# Display.net
KiCad netlist of a schematic drawn in Altium Designer
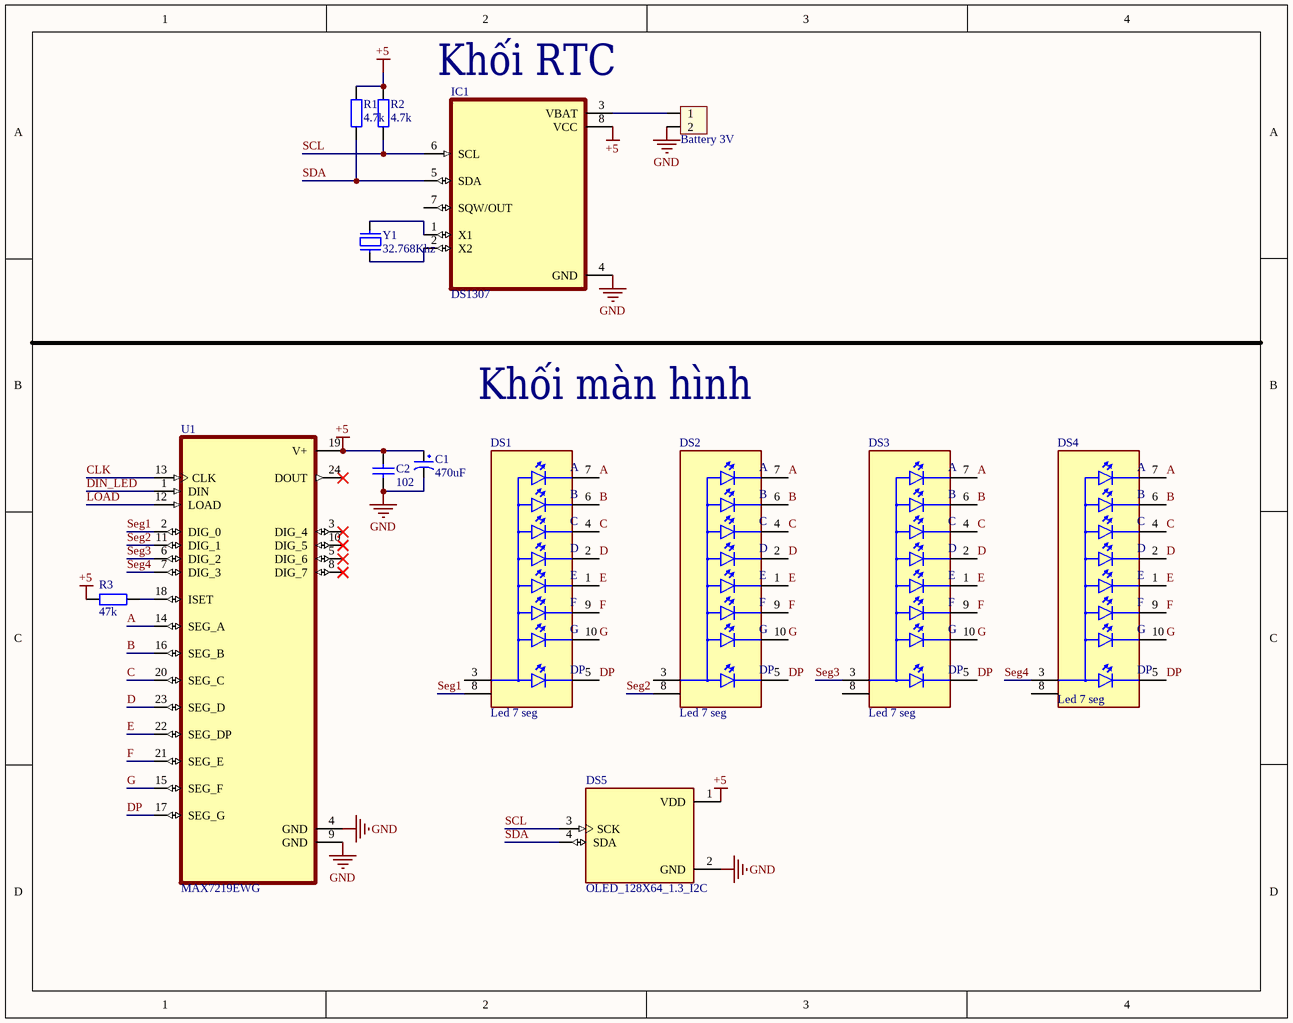
[diagram p0: Display.SchDoc]

(export (version "E")
  (design (tool "Eeschema 10.0.6"))
  (components
    (comp (ref "C1")
      (value "470uF")
      (footprint "TU HOA 8mm")
      (description "Cắm")
      (libsource (lib "Capacitor") (part "Tu Hoa 470uF 50V 10x17"))
    )
    (comp (ref "C2")
      (value "102")
      (footprint "tu 1206")
      (description "Dán")
      (libsource (lib "Capacitor") (part "Tu 1206 102 50V 10%"))
    )
    (comp (ref "DS1")
      (value "Led 7 seg")
      (footprint "LED_7Seg_1Inch:2.3_7-SEG_DIS")
      (fields (field (name "MF") "Broadcom Limited") (field (name "MP") "HDSP-511Y"))
      (libsource (lib "HDSP-511Y") (part "HDSP-511Y"))
    )
    (comp (ref "DS2")
      (value "Led 7 seg")
      (footprint "LED_7Seg_1Inch:2.3_7-SEG_DIS")
      (fields (field (name "MF") "Broadcom Limited") (field (name "MP") "HDSP-511Y"))
      (libsource (lib "HDSP-511Y") (part "HDSP-511Y"))
    )
    (comp (ref "DS3")
      (value "Led 7 seg")
      (footprint "LED_7Seg_1Inch:2.3_7-SEG_DIS")
      (fields (field (name "MF") "Broadcom Limited") (field (name "MP") "HDSP-511Y"))
      (libsource (lib "HDSP-511Y") (part "HDSP-511Y"))
    )
    (comp (ref "DS4")
      (value "Led 7 seg")
      (footprint "LED_7Seg_1Inch:2.3_7-SEG_DIS")
      (fields (field (name "MF") "Broadcom Limited") (field (name "MP") "HDSP-511Y"))
      (libsource (lib "HDSP-511Y") (part "HDSP-511Y"))
    )
    (comp (ref "DS5")
      (value "OLED_128X64_1.3_I2C")
      (footprint "LCD_OLED_128X64_1.3_I2C")
      (fields
        (field (name "MF") "UNIVERSAL-SOLDER Electronics Ltd")
        (field (name "MP") "OLED 128x64 1.3&quot; I2C")
      )
      (libsource (lib "OLED_128X64_1.3_I2C") (part "OLED_128X64_1.3_I2C"))
    )
    (comp (ref "H1")
      (value "Battery 3V")
      (footprint "Header 2P DC 2.54")
      (description "Cắm")
      (libsource (lib "Header") (part "Header 2P 2.54 Duc Cong"))
    )
    (comp (ref "IC1")
      (value "DS1307")
      (footprint "DIP794W47P254L991H457Q8")
      (description "Real Time Clock (RTC) IC Clock/Calendar 56B IÂ²C, 2-Wire Serial 8-SOIC (0.154, 3.90mm Width)")
      (fields (field (name "MF") "Maxim Integrated"))
      (libsource (lib "DS1307") (part "DS1307"))
    )
    (comp (ref "R1")
      (value "4.7k")
      (footprint "tro smd 1206")
      (description "Dán")
      (libsource (lib "Resistor") (part "Tro 1206 5% 1k"))
    )
    (comp (ref "R2")
      (value "4.7k")
      (footprint "tro smd 1206")
      (description "Dán")
      (libsource (lib "Resistor") (part "Tro 1206 5% 1k"))
    )
    (comp (ref "R3")
      (value "47k")
      (footprint "tro smd 1206")
      (description "Dán")
      (libsource (lib "Resistor") (part "Tro 1206 5% 1k"))
    )
    (comp (ref "U1")
      (value "MAX7219EWG")
      (footprint "DIP794W47P254L3054H457Q24")
      (description "LED Driver 64 Segment 330000uA Supply Current 24-Pin SOIC W Tube")
      (fields (field (name "MF") "Analog Devices") (field (name "MP") "MAX7219EWG+"))
      (libsource (lib "MAX7219EWG") (part "MAX7219EWG"))
    )
    (comp (ref "Y1")
      (value "32.768Khz")
      (footprint "Thach Anh 2 Chan 32,768 KHz")
      (description "Crystal For all Crystal 2pin.")
      (libsource (lib "Component") (part "Thach Anh 2 chan Cam"))
    )
  )
  (nets
    (net (code "1") (name "+5") (class "Default")
      (node (ref "C1") (pin "1") (pinfunction "1_1") (pintype "passive"))
      (node (ref "C2") (pin "1") (pinfunction "1_1") (pintype "passive"))
      (node (ref "DS5") (pin "1") (pinfunction "VDD_1") (pintype "power_in"))
      (node (ref "IC1") (pin "8") (pinfunction "VCC_8") (pintype "power_in"))
      (node (ref "R1") (pin "2") (pinfunction "2_2") (pintype "passive"))
      (node (ref "R2") (pin "2") (pinfunction "2_2") (pintype "passive"))
      (node (ref "R3") (pin "2") (pinfunction "2_2") (pintype "passive"))
      (node (ref "U1") (pin "19") (pinfunction "V+_19") (pintype "power_in"))
    )
    (net (code "2") (name "/A") (class "Default")
      (node (ref "DS1") (pin "7") (pinfunction "A_7") (pintype "passive"))
      (node (ref "DS2") (pin "7") (pinfunction "A_7") (pintype "passive"))
      (node (ref "DS3") (pin "7") (pinfunction "A_7") (pintype "passive"))
      (node (ref "DS4") (pin "7") (pinfunction "A_7") (pintype "passive"))
      (node (ref "U1") (pin "14") (pinfunction "SEG_A_14") (pintype "bidirectional"))
    )
    (net (code "3") (name "/B") (class "Default")
      (node (ref "DS1") (pin "6") (pinfunction "B_6") (pintype "passive"))
      (node (ref "DS2") (pin "6") (pinfunction "B_6") (pintype "passive"))
      (node (ref "DS3") (pin "6") (pinfunction "B_6") (pintype "passive"))
      (node (ref "DS4") (pin "6") (pinfunction "B_6") (pintype "passive"))
      (node (ref "U1") (pin "16") (pinfunction "SEG_B_16") (pintype "bidirectional"))
    )
    (net (code "4") (name "/C") (class "Default")
      (node (ref "DS1") (pin "4") (pinfunction "C_4") (pintype "passive"))
      (node (ref "DS2") (pin "4") (pinfunction "C_4") (pintype "passive"))
      (node (ref "DS3") (pin "4") (pinfunction "C_4") (pintype "passive"))
      (node (ref "DS4") (pin "4") (pinfunction "C_4") (pintype "passive"))
      (node (ref "U1") (pin "20") (pinfunction "SEG_C_20") (pintype "bidirectional"))
    )
    (net (code "5") (name "/CLK") (class "Default")
      (node (ref "U1") (pin "13") (pinfunction "CLK_13") (pintype "input"))
    )
    (net (code "6") (name "/D") (class "Default")
      (node (ref "DS1") (pin "2") (pinfunction "D_2") (pintype "passive"))
      (node (ref "DS2") (pin "2") (pinfunction "D_2") (pintype "passive"))
      (node (ref "DS3") (pin "2") (pinfunction "D_2") (pintype "passive"))
      (node (ref "DS4") (pin "2") (pinfunction "D_2") (pintype "passive"))
      (node (ref "U1") (pin "23") (pinfunction "SEG_D_23") (pintype "bidirectional"))
    )
    (net (code "7") (name "/DIN_LED") (class "Default")
      (node (ref "U1") (pin "1") (pinfunction "DIN_1") (pintype "input"))
    )
    (net (code "8") (name "/DP") (class "Default")
      (node (ref "DS1") (pin "5") (pinfunction "DP_5") (pintype "passive"))
      (node (ref "DS2") (pin "5") (pinfunction "DP_5") (pintype "passive"))
      (node (ref "DS3") (pin "5") (pinfunction "DP_5") (pintype "passive"))
      (node (ref "DS4") (pin "5") (pinfunction "DP_5") (pintype "passive"))
      (node (ref "U1") (pin "17") (pinfunction "SEG_G_17") (pintype "bidirectional"))
    )
    (net (code "9") (name "/E") (class "Default")
      (node (ref "DS1") (pin "1") (pinfunction "E_1") (pintype "passive"))
      (node (ref "DS2") (pin "1") (pinfunction "E_1") (pintype "passive"))
      (node (ref "DS3") (pin "1") (pinfunction "E_1") (pintype "passive"))
      (node (ref "DS4") (pin "1") (pinfunction "E_1") (pintype "passive"))
      (node (ref "U1") (pin "22") (pinfunction "SEG_DP_22") (pintype "bidirectional"))
    )
    (net (code "10") (name "/F") (class "Default")
      (node (ref "DS1") (pin "9") (pinfunction "F_9") (pintype "passive"))
      (node (ref "DS2") (pin "9") (pinfunction "F_9") (pintype "passive"))
      (node (ref "DS3") (pin "9") (pinfunction "F_9") (pintype "passive"))
      (node (ref "DS4") (pin "9") (pinfunction "F_9") (pintype "passive"))
      (node (ref "U1") (pin "21") (pinfunction "SEG_E_21") (pintype "bidirectional"))
    )
    (net (code "11") (name "/G") (class "Default")
      (node (ref "DS1") (pin "10") (pinfunction "G_10") (pintype "passive"))
      (node (ref "DS2") (pin "10") (pinfunction "G_10") (pintype "passive"))
      (node (ref "DS3") (pin "10") (pinfunction "G_10") (pintype "passive"))
      (node (ref "DS4") (pin "10") (pinfunction "G_10") (pintype "passive"))
      (node (ref "U1") (pin "15") (pinfunction "SEG_F_15") (pintype "bidirectional"))
    )
    (net (code "12") (name "/LOAD") (class "Default")
      (node (ref "U1") (pin "12") (pinfunction "LOAD_12") (pintype "input"))
    )
    (net (code "13") (name "/SCL") (class "Default")
      (node (ref "DS5") (pin "3") (pinfunction "SCK_3") (pintype "input"))
      (node (ref "IC1") (pin "6") (pinfunction "SCL_6") (pintype "input"))
      (node (ref "R2") (pin "1") (pinfunction "1_1") (pintype "passive"))
    )
    (net (code "14") (name "/SDA") (class "Default")
      (node (ref "DS5") (pin "4") (pinfunction "SDA_4") (pintype "bidirectional"))
      (node (ref "IC1") (pin "5") (pinfunction "SDA_5") (pintype "bidirectional"))
      (node (ref "R1") (pin "1") (pinfunction "1_1") (pintype "passive"))
    )
    (net (code "15") (name "/Seg1") (class "Default")
      (node (ref "DS1") (pin "8") (pinfunction "COM_8") (pintype "passive"))
      (node (ref "U1") (pin "2") (pinfunction "DIG_0_2") (pintype "bidirectional"))
    )
    (net (code "16") (name "/Seg2") (class "Default")
      (node (ref "DS2") (pin "8") (pinfunction "COM_8") (pintype "passive"))
      (node (ref "U1") (pin "11") (pinfunction "DIG_1_11") (pintype "bidirectional"))
    )
    (net (code "17") (name "/Seg3") (class "Default")
      (node (ref "DS3") (pin "3") (pinfunction "COM_3") (pintype "passive"))
      (node (ref "U1") (pin "6") (pinfunction "DIG_2_6") (pintype "bidirectional"))
    )
    (net (code "18") (name "/Seg4") (class "Default")
      (node (ref "DS4") (pin "3") (pinfunction "COM_3") (pintype "passive"))
      (node (ref "U1") (pin "7") (pinfunction "DIG_3_7") (pintype "bidirectional"))
    )
    (net (code "19") (name "GND") (class "Default")
      (node (ref "C1") (pin "2") (pinfunction "2_2") (pintype "passive"))
      (node (ref "C2") (pin "2") (pinfunction "2_2") (pintype "passive"))
      (node (ref "DS5") (pin "2") (pinfunction "GND_2") (pintype "power_in"))
      (node (ref "H1") (pin "2") (pinfunction "2_2") (pintype "passive"))
      (node (ref "IC1") (pin "4") (pinfunction "GND_4") (pintype "power_in"))
      (node (ref "U1") (pin "4") (pinfunction "GND_4") (pintype "power_in"))
      (node (ref "U1") (pin "9") (pinfunction "GND_9") (pintype "power_in"))
    )
    (net (code "20") (name "Net-(IC1-VBAT)") (class "Default")
      (node (ref "H1") (pin "1") (pinfunction "1_1") (pintype "passive"))
      (node (ref "IC1") (pin "3") (pinfunction "VBAT_3") (pintype "power_in"))
    )
    (net (code "21") (name "Net-(IC1-X1)") (class "Default")
      (node (ref "IC1") (pin "1") (pinfunction "X1_1") (pintype "bidirectional"))
      (node (ref "Y1") (pin "2") (pinfunction "2_2") (pintype "passive"))
    )
    (net (code "22") (name "Net-(IC1-X2)") (class "Default")
      (node (ref "IC1") (pin "2") (pinfunction "X2_2") (pintype "bidirectional"))
      (node (ref "Y1") (pin "1") (pinfunction "1_1") (pintype "passive"))
    )
    (net (code "23") (name "Net-(U1-ISET)") (class "Default")
      (node (ref "R3") (pin "1") (pinfunction "1_1") (pintype "passive"))
      (node (ref "U1") (pin "18") (pinfunction "ISET_18") (pintype "bidirectional"))
    )
    (net (code "24") (name "unconnected-(DS1-COM-Pad3)") (class "Default")
      (node (ref "DS1") (pin "3") (pinfunction "COM_3") (pintype "passive"))
    )
    (net (code "25") (name "unconnected-(DS2-COM-Pad3)") (class "Default")
      (node (ref "DS2") (pin "3") (pinfunction "COM_3") (pintype "passive"))
    )
    (net (code "26") (name "unconnected-(DS3-COM-Pad8)") (class "Default")
      (node (ref "DS3") (pin "8") (pinfunction "COM_8") (pintype "passive"))
    )
    (net (code "27") (name "unconnected-(DS4-COM-Pad8)") (class "Default")
      (node (ref "DS4") (pin "8") (pinfunction "COM_8") (pintype "passive"))
    )
    (net (code "28") (name "unconnected-(IC1-SQW{slash}OUT-Pad7)") (class "Default")
      (node (ref "IC1") (pin "7") (pinfunction "SQW/OUT_7") (pintype "bidirectional"))
    )
    (net (code "29") (name "unconnected-(U1-DIG_4-Pad3)") (class "Default")
      (node (ref "U1") (pin "3") (pinfunction "DIG_4_3") (pintype "bidirectional+no_connect"))
    )
    (net (code "30") (name "unconnected-(U1-DIG_5-Pad10)") (class "Default")
      (node (ref "U1") (pin "10") (pinfunction "DIG_5_10") (pintype "bidirectional+no_connect"))
    )
    (net (code "31") (name "unconnected-(U1-DIG_6-Pad5)") (class "Default")
      (node (ref "U1") (pin "5") (pinfunction "DIG_6_5") (pintype "bidirectional+no_connect"))
    )
    (net (code "32") (name "unconnected-(U1-DIG_7-Pad8)") (class "Default")
      (node (ref "U1") (pin "8") (pinfunction "DIG_7_8") (pintype "bidirectional+no_connect"))
    )
    (net (code "33") (name "unconnected-(U1-DOUT-Pad24)") (class "Default")
      (node (ref "U1") (pin "24") (pinfunction "DOUT_24") (pintype "output+no_connect"))
    )
  )
)
